# 4_LPC1850__Others.net
KiCad netlist of a schematic drawn in Altium Designer
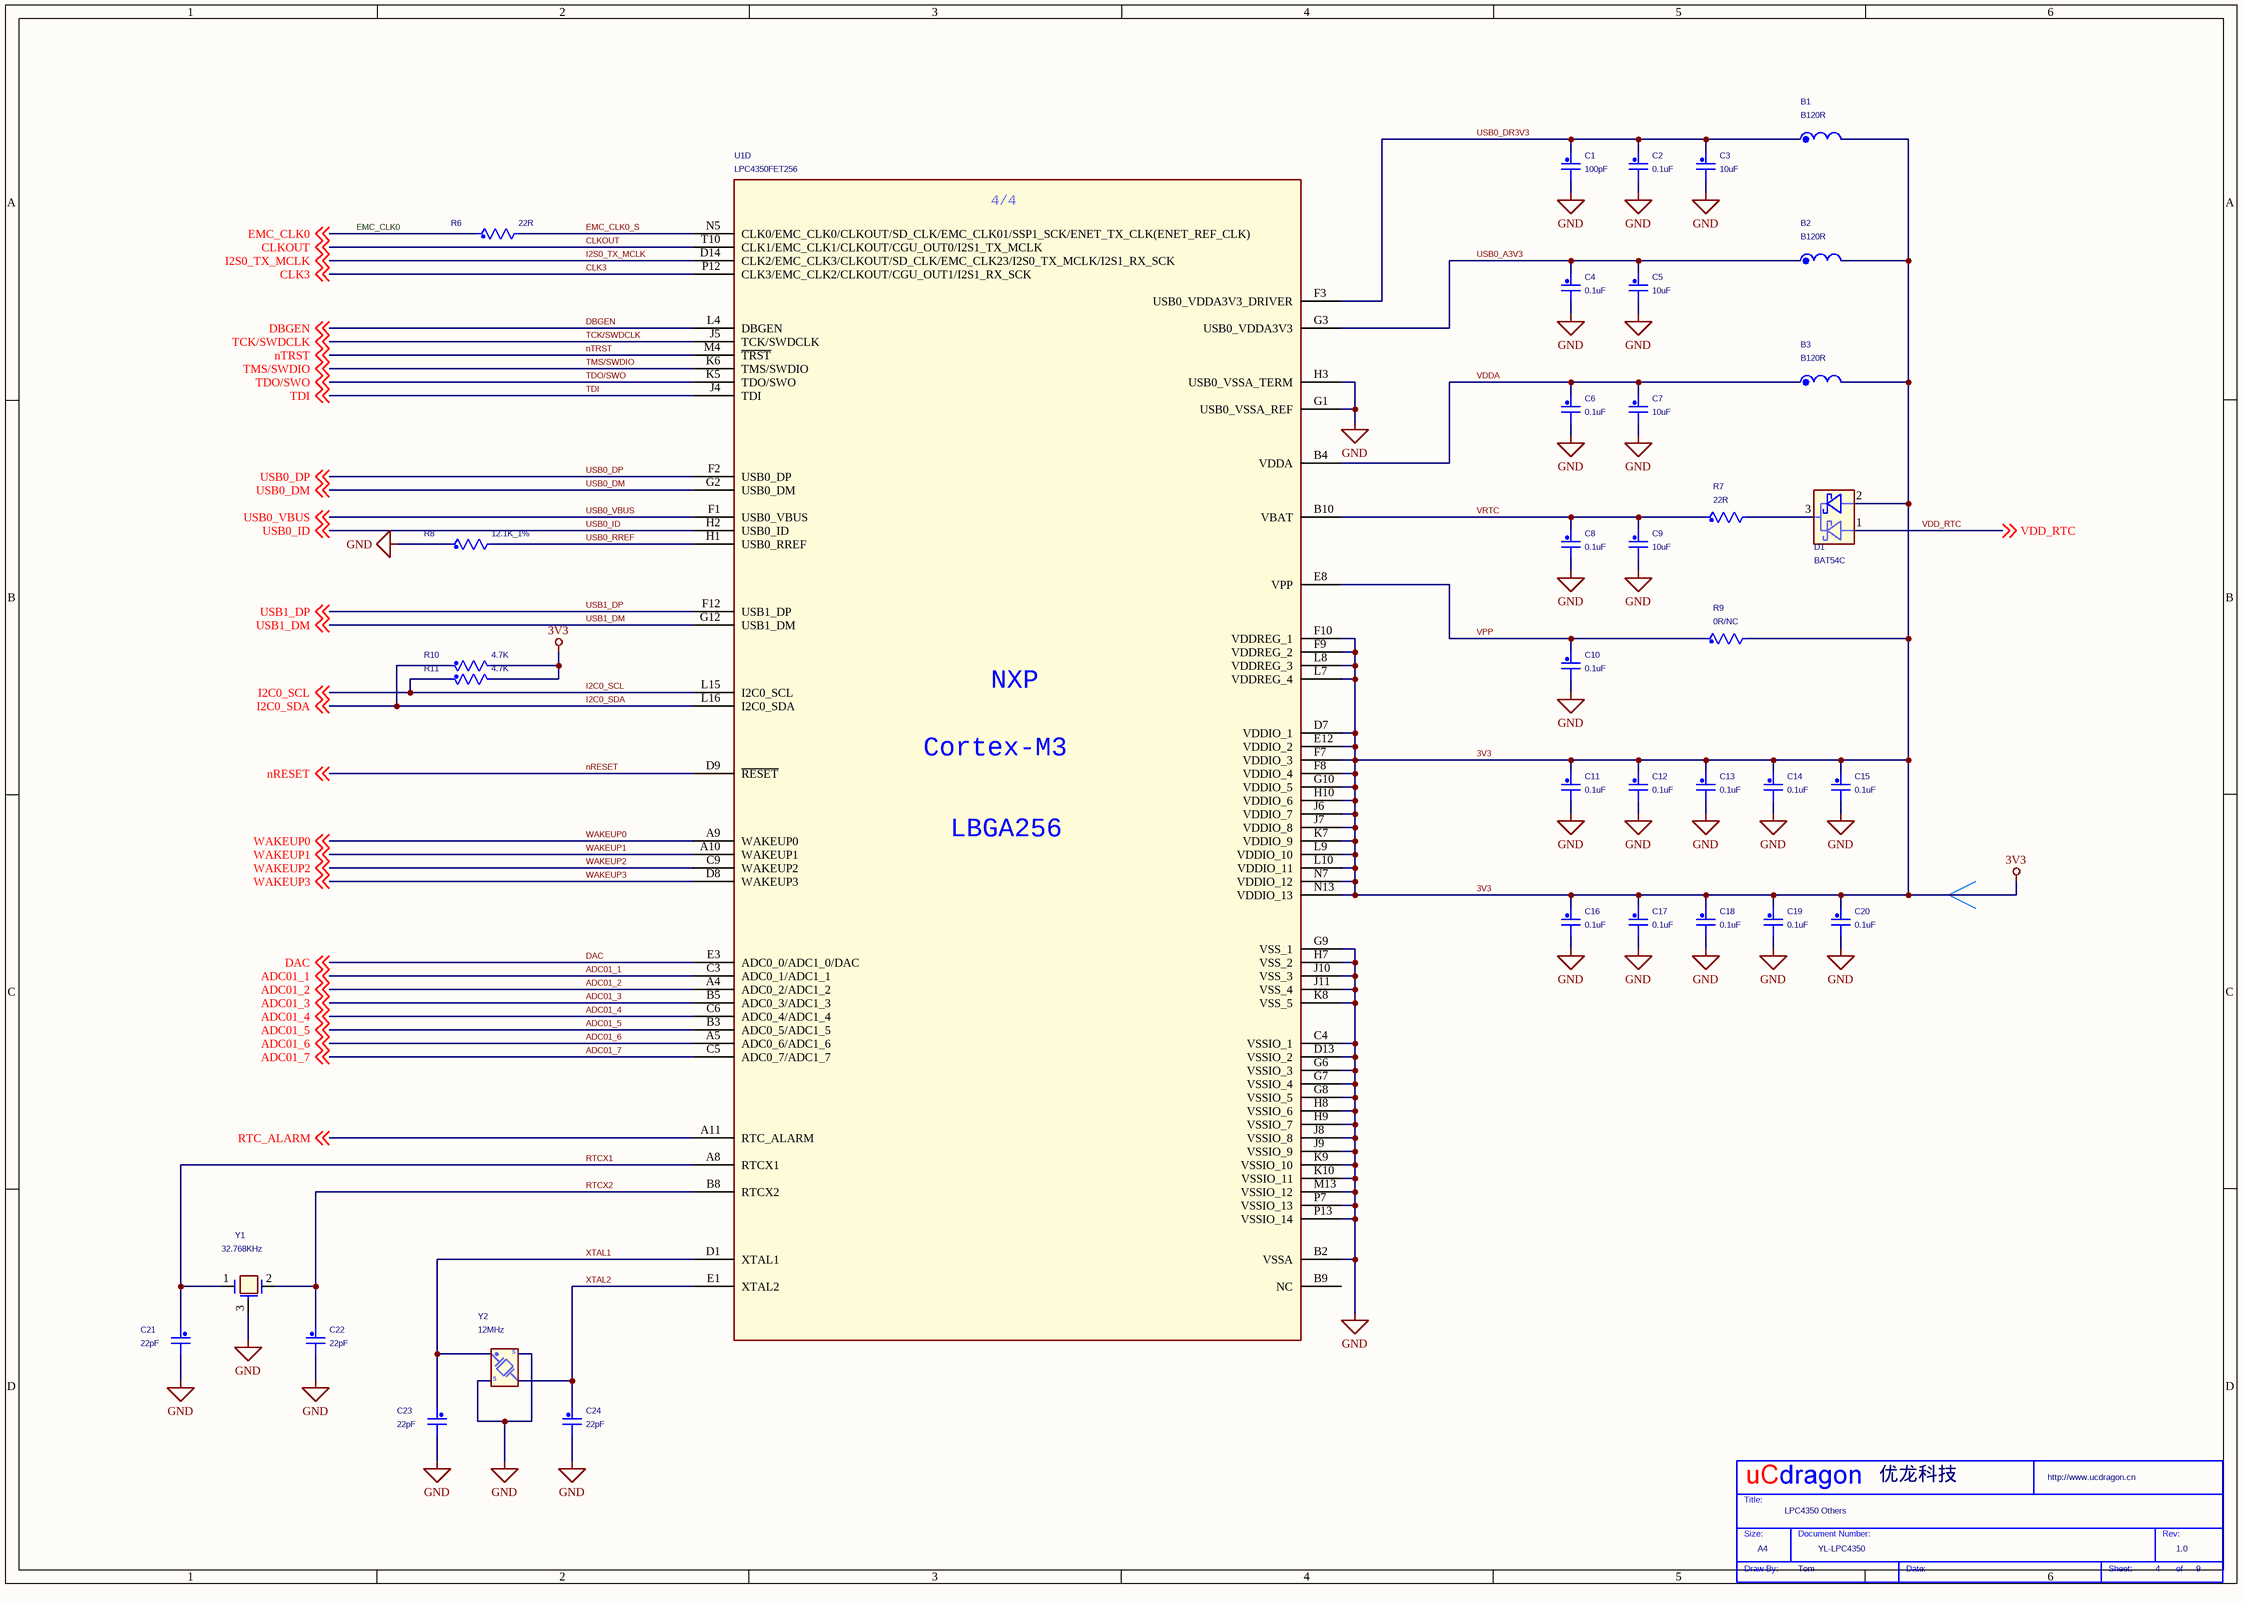
[diagram p0: 4) LPC1850_ Others.SchDoc]

(export (version "E")
  (design (tool "Eeschema 10.0.6"))
  (components
    (comp (ref "*")
      (value "My Title 0")
      (fields
        (field (name "COMPANY") "优龙科技")
        (field (name "DRAWING") "Tom")
        (field (name "WEBSITE") "http://www.ucdragon.cn")
        (field (name "DOC") "YL-LPC4350")
        (field (name "REVCODE") "1.0")
        (field (name "TITLE") "LPC4350 Others")
        (field (name "PAGE SIZE") "A4")
        (field (name "PAGE NUMBER") "4")
        (field (name "PAGE COUNT") "9")
      )
      (libsource (lib "*") (part "My Title 0"))
    )
    (comp (ref "B1") (value "B120R") (libsource (lib "*") (part "Inductor PWR-SMD")))
    (comp (ref "B2") (value "B120R") (libsource (lib "*") (part "Inductor PWR-SMD")))
    (comp (ref "B3") (value "B120R") (libsource (lib "*") (part "Inductor PWR-SMD")))
    (comp (ref "C1")
      (value "100pF")
      (footprint "CAP0805")
      (fields (field (name "VOLTAGE") "16V"))
      (libsource (lib "*") (part "C_Generic"))
    )
    (comp (ref "C2")
      (value "0.1uF")
      (footprint "CAP0805")
      (fields (field (name "VOLTAGE") "16V"))
      (libsource (lib "*") (part "C_Generic"))
    )
    (comp (ref "C3")
      (value "10uF")
      (footprint "CAP0805")
      (fields (field (name "VOLTAGE") "16V"))
      (libsource (lib "*") (part "C_Generic"))
    )
    (comp (ref "C4")
      (value "0.1uF")
      (footprint "CAP0805")
      (fields (field (name "VOLTAGE") "16V"))
      (libsource (lib "*") (part "C_Generic"))
    )
    (comp (ref "C5")
      (value "10uF")
      (footprint "CAP0805")
      (fields (field (name "VOLTAGE") "16V"))
      (libsource (lib "*") (part "C_Generic"))
    )
    (comp (ref "C6")
      (value "0.1uF")
      (footprint "CAP0805")
      (fields (field (name "VOLTAGE") "16V"))
      (libsource (lib "*") (part "C_Generic"))
    )
    (comp (ref "C7")
      (value "10uF")
      (footprint "CAP0805")
      (fields (field (name "VOLTAGE") "16V"))
      (libsource (lib "*") (part "C_Generic"))
    )
    (comp (ref "C8")
      (value "0.1uF")
      (footprint "CAP0805")
      (fields (field (name "VOLTAGE") "16V"))
      (libsource (lib "*") (part "C_Generic"))
    )
    (comp (ref "C9")
      (value "10uF")
      (footprint "CAP0805")
      (fields (field (name "VOLTAGE") "16V"))
      (libsource (lib "*") (part "C_Generic"))
    )
    (comp (ref "C10")
      (value "0.1uF")
      (footprint "CAP0805")
      (fields (field (name "VOLTAGE") "16V"))
      (libsource (lib "*") (part "C_Generic"))
    )
    (comp (ref "C11")
      (value "0.1uF")
      (footprint "CAP0805")
      (fields (field (name "VOLTAGE") "16V"))
      (libsource (lib "*") (part "C_Generic"))
    )
    (comp (ref "C12")
      (value "0.1uF")
      (footprint "CAP0805")
      (fields (field (name "VOLTAGE") "16V"))
      (libsource (lib "*") (part "C_Generic"))
    )
    (comp (ref "C13")
      (value "0.1uF")
      (footprint "CAP0805")
      (fields (field (name "VOLTAGE") "16V"))
      (libsource (lib "*") (part "C_Generic"))
    )
    (comp (ref "C14")
      (value "0.1uF")
      (footprint "CAP0805")
      (fields (field (name "VOLTAGE") "16V"))
      (libsource (lib "*") (part "C_Generic"))
    )
    (comp (ref "C15")
      (value "0.1uF")
      (footprint "CAP0805")
      (fields (field (name "VOLTAGE") "16V"))
      (libsource (lib "*") (part "C_Generic"))
    )
    (comp (ref "C16")
      (value "0.1uF")
      (footprint "CAP0805")
      (fields (field (name "VOLTAGE") "16V"))
      (libsource (lib "*") (part "C_Generic"))
    )
    (comp (ref "C17")
      (value "0.1uF")
      (footprint "CAP0805")
      (fields (field (name "VOLTAGE") "16V"))
      (libsource (lib "*") (part "C_Generic"))
    )
    (comp (ref "C18")
      (value "0.1uF")
      (footprint "CAP0805")
      (fields (field (name "VOLTAGE") "16V"))
      (libsource (lib "*") (part "C_Generic"))
    )
    (comp (ref "C19")
      (value "0.1uF")
      (footprint "CAP0805")
      (fields (field (name "VOLTAGE") "16V"))
      (libsource (lib "*") (part "C_Generic"))
    )
    (comp (ref "C20")
      (value "0.1uF")
      (footprint "CAP0805")
      (fields (field (name "VOLTAGE") "16V"))
      (libsource (lib "*") (part "C_Generic"))
    )
    (comp (ref "C21")
      (value "22pF")
      (footprint "CAP0805")
      (fields (field (name "VOLTAGE") "16V"))
      (libsource (lib "*") (part "C_Generic"))
    )
    (comp (ref "C22")
      (value "22pF")
      (footprint "CAP0805")
      (fields (field (name "VOLTAGE") "16V"))
      (libsource (lib "*") (part "C_Generic"))
    )
    (comp (ref "C23")
      (value "22pF")
      (footprint "CAP0805")
      (fields (field (name "VOLTAGE") "16V"))
      (libsource (lib "*") (part "C_Generic"))
    )
    (comp (ref "C24")
      (value "22pF")
      (footprint "CAP0805")
      (fields (field (name "VOLTAGE") "16V"))
      (libsource (lib "*") (part "C_Generic"))
    )
    (comp (ref "D1") (value "BAT54C") (libsource (lib "*") (part "BAT54C")))
    (comp (ref "R6") (value "22R") (libsource (lib "*") (part "R_Generic_Dup2")))
    (comp (ref "R7") (value "22R") (libsource (lib "*") (part "R_Generic_Dup2")))
    (comp (ref "R8") (value "12.1K_1%") (libsource (lib "*") (part "R_Generic_Dup2")))
    (comp (ref "R9") (value "0R/NC") (libsource (lib "*") (part "R_Generic_Dup2")))
    (comp (ref "R10") (value "4.7K") (libsource (lib "*") (part "R_Generic_Dup1")))
    (comp (ref "R11") (value "4.7K") (libsource (lib "*") (part "R_Generic_Dup1")))
    (comp (ref "U1")
      (value "LPC4350FET256")
      (footprint "LBGA256")
      (libsource (lib "*") (part "LPC4350FET256"))
    )
    (comp (ref "Y1") (value "32.768KHz") (libsource (lib "*") (part "XTAL1")))
    (comp (ref "Y2") (value "12MHz") (footprint "Y3225") (libsource (lib "*") (part "CRYSTAL 3225-2")))
  )
  (nets
    (net (code "1") (name "/EMC_CLK0_S") (class "Default")
      (node (ref "R6") (pin "2") (pinfunction "2_2") (pintype "passive"))
      (node (ref "U1") (pin "N5") (pinfunction "CLK0/EMC_CLK0/CLKOUT/SD_CLK/EMC_CLK01/SSP1_SCK/ENET_TX_CLK(ENET_REF_CLK)_N5") (pintype "passive"))
    )
    (net (code "2") (name "/RTCX1") (class "Default")
      (node (ref "C21") (pin "1") (pinfunction "1_1") (pintype "passive"))
      (node (ref "U1") (pin "A8") (pinfunction "RTCX1_A8") (pintype "passive"))
      (node (ref "Y1") (pin "1") (pinfunction "1_1") (pintype "passive"))
    )
    (net (code "3") (name "/RTCX2") (class "Default")
      (node (ref "C22") (pin "1") (pinfunction "1_1") (pintype "passive"))
      (node (ref "U1") (pin "B8") (pinfunction "RTCX2_B8") (pintype "passive"))
      (node (ref "Y1") (pin "2") (pinfunction "2_2") (pintype "passive"))
    )
    (net (code "4") (name "/USB0_A3V3") (class "Default")
      (node (ref "B2") (pin "1") (pinfunction "1_1") (pintype "passive"))
      (node (ref "C4") (pin "1") (pinfunction "1_1") (pintype "passive"))
      (node (ref "C5") (pin "1") (pinfunction "1_1") (pintype "passive"))
      (node (ref "U1") (pin "G3") (pinfunction "USB0_VDDA3V3_G3") (pintype "passive"))
    )
    (net (code "5") (name "/USB0_DR3V3") (class "Default")
      (node (ref "B1") (pin "1") (pinfunction "1_1") (pintype "passive"))
      (node (ref "C1") (pin "1") (pinfunction "1_1") (pintype "passive"))
      (node (ref "C2") (pin "1") (pinfunction "1_1") (pintype "passive"))
      (node (ref "C3") (pin "1") (pinfunction "1_1") (pintype "passive"))
      (node (ref "U1") (pin "F3") (pinfunction "USB0_VDDA3V3_DRIVER_F3") (pintype "passive"))
    )
    (net (code "6") (name "/USB0_RREF") (class "Default")
      (node (ref "R8") (pin "2") (pinfunction "2_2") (pintype "passive"))
      (node (ref "U1") (pin "H1") (pinfunction "USB0_RREF_H1") (pintype "passive"))
    )
    (net (code "7") (name "/VDDA") (class "Default")
      (node (ref "B3") (pin "1") (pinfunction "1_1") (pintype "passive"))
      (node (ref "C6") (pin "1") (pinfunction "1_1") (pintype "passive"))
      (node (ref "C7") (pin "1") (pinfunction "1_1") (pintype "passive"))
      (node (ref "U1") (pin "B4") (pinfunction "VDDA_B4") (pintype "passive"))
    )
    (net (code "8") (name "/VPP") (class "Default")
      (node (ref "C10") (pin "1") (pinfunction "1_1") (pintype "passive"))
      (node (ref "R9") (pin "1") (pinfunction "1_1") (pintype "passive"))
      (node (ref "U1") (pin "E8") (pinfunction "VPP_E8") (pintype "passive"))
    )
    (net (code "9") (name "/VRTC") (class "Default")
      (node (ref "C8") (pin "1") (pinfunction "1_1") (pintype "passive"))
      (node (ref "C9") (pin "1") (pinfunction "1_1") (pintype "passive"))
      (node (ref "R7") (pin "1") (pinfunction "1_1") (pintype "passive"))
      (node (ref "U1") (pin "B10") (pinfunction "VBAT_B10") (pintype "passive"))
    )
    (net (code "10") (name "/XTAL1") (class "Default")
      (node (ref "C23") (pin "1") (pinfunction "1_1") (pintype "passive"))
      (node (ref "U1") (pin "D1") (pinfunction "XTAL1_D1") (pintype "passive"))
      (node (ref "Y2") (pin "1") (pinfunction "1_1") (pintype "passive"))
    )
    (net (code "11") (name "/XTAL2") (class "Default")
      (node (ref "C24") (pin "1") (pinfunction "1_1") (pintype "passive"))
      (node (ref "U1") (pin "E1") (pinfunction "XTAL2_E1") (pintype "passive"))
      (node (ref "Y2") (pin "3") (pinfunction "3_3") (pintype "passive"))
    )
    (net (code "12") (name "3V3") (class "Default")
      (node (ref "B1") (pin "2") (pinfunction "2_2") (pintype "passive"))
      (node (ref "B2") (pin "2") (pinfunction "2_2") (pintype "passive"))
      (node (ref "B3") (pin "2") (pinfunction "2_2") (pintype "passive"))
      (node (ref "C11") (pin "1") (pinfunction "1_1") (pintype "passive"))
      (node (ref "C12") (pin "1") (pinfunction "1_1") (pintype "passive"))
      (node (ref "C13") (pin "1") (pinfunction "1_1") (pintype "passive"))
      (node (ref "C14") (pin "1") (pinfunction "1_1") (pintype "passive"))
      (node (ref "C15") (pin "1") (pinfunction "1_1") (pintype "passive"))
      (node (ref "C16") (pin "1") (pinfunction "1_1") (pintype "passive"))
      (node (ref "C17") (pin "1") (pinfunction "1_1") (pintype "passive"))
      (node (ref "C18") (pin "1") (pinfunction "1_1") (pintype "passive"))
      (node (ref "C19") (pin "1") (pinfunction "1_1") (pintype "passive"))
      (node (ref "C20") (pin "1") (pinfunction "1_1") (pintype "passive"))
      (node (ref "D1") (pin "2") (pinfunction "K_2") (pintype "passive"))
      (node (ref "R10") (pin "2") (pinfunction "2_2") (pintype "passive"))
      (node (ref "R11") (pin "2") (pinfunction "2_2") (pintype "passive"))
      (node (ref "R9") (pin "2") (pinfunction "2_2") (pintype "passive"))
      (node (ref "U1") (pin "D7") (pinfunction "VDDIO_1_D7") (pintype "passive"))
      (node (ref "U1") (pin "E12") (pinfunction "VDDIO_2_E12") (pintype "passive"))
      (node (ref "U1") (pin "F10") (pinfunction "VDDREG_1_F10") (pintype "passive"))
      (node (ref "U1") (pin "F7") (pinfunction "VDDIO_3_F7") (pintype "passive"))
      (node (ref "U1") (pin "F8") (pinfunction "VDDIO_4_F8") (pintype "passive"))
      (node (ref "U1") (pin "F9") (pinfunction "VDDREG_2_F9") (pintype "passive"))
      (node (ref "U1") (pin "G10") (pinfunction "VDDIO_5_G10") (pintype "passive"))
      (node (ref "U1") (pin "H10") (pinfunction "VDDIO_6_H10") (pintype "passive"))
      (node (ref "U1") (pin "J6") (pinfunction "VDDIO_7_J6") (pintype "passive"))
      (node (ref "U1") (pin "J7") (pinfunction "VDDIO_8_J7") (pintype "passive"))
      (node (ref "U1") (pin "K7") (pinfunction "VDDIO_9_K7") (pintype "passive"))
      (node (ref "U1") (pin "L10") (pinfunction "VDDIO_11_L10") (pintype "passive"))
      (node (ref "U1") (pin "L7") (pinfunction "VDDREG_4_L7") (pintype "passive"))
      (node (ref "U1") (pin "L8") (pinfunction "VDDREG_3_L8") (pintype "passive"))
      (node (ref "U1") (pin "L9") (pinfunction "VDDIO_10_L9") (pintype "passive"))
      (node (ref "U1") (pin "N13") (pinfunction "VDDIO_13_N13") (pintype "passive"))
      (node (ref "U1") (pin "N7") (pinfunction "VDDIO_12_N7") (pintype "passive"))
    )
    (net (code "13") (name "ADC01_1") (class "Default")
      (node (ref "U1") (pin "C3") (pinfunction "ADC0_1/ADC1_1_C3") (pintype "passive"))
    )
    (net (code "14") (name "ADC01_2") (class "Default")
      (node (ref "U1") (pin "A4") (pinfunction "ADC0_2/ADC1_2_A4") (pintype "passive"))
    )
    (net (code "15") (name "ADC01_3") (class "Default")
      (node (ref "U1") (pin "B5") (pinfunction "ADC0_3/ADC1_3_B5") (pintype "passive"))
    )
    (net (code "16") (name "ADC01_4") (class "Default")
      (node (ref "U1") (pin "C6") (pinfunction "ADC0_4/ADC1_4_C6") (pintype "passive"))
    )
    (net (code "17") (name "ADC01_5") (class "Default")
      (node (ref "U1") (pin "B3") (pinfunction "ADC0_5/ADC1_5_B3") (pintype "passive"))
    )
    (net (code "18") (name "ADC01_6") (class "Default")
      (node (ref "U1") (pin "A5") (pinfunction "ADC0_6/ADC1_6_A5") (pintype "passive"))
    )
    (net (code "19") (name "ADC01_7") (class "Default")
      (node (ref "U1") (pin "C5") (pinfunction "ADC0_7/ADC1_7_C5") (pintype "passive"))
    )
    (net (code "20") (name "CLK3") (class "Default")
      (node (ref "U1") (pin "P12") (pinfunction "CLK3/EMC_CLK2/CLKOUT/CGU_OUT1/I2S1_RX_SCK_P12") (pintype "passive"))
    )
    (net (code "21") (name "CLKOUT") (class "Default")
      (node (ref "U1") (pin "T10") (pinfunction "CLK1/EMC_CLK1/CLKOUT/CGU_OUT0/I2S1_TX_MCLK_T10") (pintype "passive"))
    )
    (net (code "22") (name "DAC") (class "Default")
      (node (ref "U1") (pin "E3") (pinfunction "ADC0_0/ADC1_0/DAC_E3") (pintype "passive"))
    )
    (net (code "23") (name "DBGEN") (class "Default")
      (node (ref "U1") (pin "L4") (pinfunction "DBGEN_L4") (pintype "passive"))
    )
    (net (code "24") (name "EMC_CLK0") (class "Default")
      (node (ref "R6") (pin "1") (pinfunction "1_1") (pintype "passive"))
    )
    (net (code "25") (name "GND") (class "Default")
      (node (ref "C1") (pin "2") (pinfunction "2_2") (pintype "passive"))
      (node (ref "C10") (pin "2") (pinfunction "2_2") (pintype "passive"))
      (node (ref "C11") (pin "2") (pinfunction "2_2") (pintype "passive"))
      (node (ref "C12") (pin "2") (pinfunction "2_2") (pintype "passive"))
      (node (ref "C13") (pin "2") (pinfunction "2_2") (pintype "passive"))
      (node (ref "C14") (pin "2") (pinfunction "2_2") (pintype "passive"))
      (node (ref "C15") (pin "2") (pinfunction "2_2") (pintype "passive"))
      (node (ref "C16") (pin "2") (pinfunction "2_2") (pintype "passive"))
      (node (ref "C17") (pin "2") (pinfunction "2_2") (pintype "passive"))
      (node (ref "C18") (pin "2") (pinfunction "2_2") (pintype "passive"))
      (node (ref "C19") (pin "2") (pinfunction "2_2") (pintype "passive"))
      (node (ref "C2") (pin "2") (pinfunction "2_2") (pintype "passive"))
      (node (ref "C20") (pin "2") (pinfunction "2_2") (pintype "passive"))
      (node (ref "C21") (pin "2") (pinfunction "2_2") (pintype "passive"))
      (node (ref "C22") (pin "2") (pinfunction "2_2") (pintype "passive"))
      (node (ref "C23") (pin "2") (pinfunction "2_2") (pintype "passive"))
      (node (ref "C24") (pin "2") (pinfunction "2_2") (pintype "passive"))
      (node (ref "C3") (pin "2") (pinfunction "2_2") (pintype "passive"))
      (node (ref "C4") (pin "2") (pinfunction "2_2") (pintype "passive"))
      (node (ref "C5") (pin "2") (pinfunction "2_2") (pintype "passive"))
      (node (ref "C6") (pin "2") (pinfunction "2_2") (pintype "passive"))
      (node (ref "C7") (pin "2") (pinfunction "2_2") (pintype "passive"))
      (node (ref "C8") (pin "2") (pinfunction "2_2") (pintype "passive"))
      (node (ref "C9") (pin "2") (pinfunction "2_2") (pintype "passive"))
      (node (ref "R8") (pin "1") (pinfunction "1_1") (pintype "passive"))
      (node (ref "U1") (pin "B2") (pinfunction "VSSA_B2") (pintype "passive"))
      (node (ref "U1") (pin "C4") (pinfunction "VSSIO_1_C4") (pintype "passive"))
      (node (ref "U1") (pin "D13") (pinfunction "VSSIO_2_D13") (pintype "passive"))
      (node (ref "U1") (pin "G1") (pinfunction "USB0_VSSA_REF_G1") (pintype "passive"))
      (node (ref "U1") (pin "G6") (pinfunction "VSSIO_3_G6") (pintype "passive"))
      (node (ref "U1") (pin "G7") (pinfunction "VSSIO_4_G7") (pintype "passive"))
      (node (ref "U1") (pin "G8") (pinfunction "VSSIO_5_G8") (pintype "passive"))
      (node (ref "U1") (pin "G9") (pinfunction "VSS_1_G9") (pintype "passive"))
      (node (ref "U1") (pin "H3") (pinfunction "USB0_VSSA_TERM_H3") (pintype "passive"))
      (node (ref "U1") (pin "H7") (pinfunction "VSS_2_H7") (pintype "passive"))
      (node (ref "U1") (pin "H8") (pinfunction "VSSIO_6_H8") (pintype "passive"))
      (node (ref "U1") (pin "H9") (pinfunction "VSSIO_7_H9") (pintype "passive"))
      (node (ref "U1") (pin "J10") (pinfunction "VSS_3_J10") (pintype "passive"))
      (node (ref "U1") (pin "J11") (pinfunction "VSS_4_J11") (pintype "passive"))
      (node (ref "U1") (pin "J8") (pinfunction "VSSIO_8_J8") (pintype "passive"))
      (node (ref "U1") (pin "J9") (pinfunction "VSSIO_9_J9") (pintype "passive"))
      (node (ref "U1") (pin "K10") (pinfunction "VSSIO_11_K10") (pintype "passive"))
      (node (ref "U1") (pin "K8") (pinfunction "VSS_5_K8") (pintype "passive"))
      (node (ref "U1") (pin "K9") (pinfunction "VSSIO_10_K9") (pintype "passive"))
      (node (ref "U1") (pin "M13") (pinfunction "VSSIO_12_M13") (pintype "passive"))
      (node (ref "U1") (pin "P13") (pinfunction "VSSIO_14_P13") (pintype "passive"))
      (node (ref "U1") (pin "P7") (pinfunction "VSSIO_13_P7") (pintype "passive"))
      (node (ref "Y1") (pin "3") (pinfunction "GND_3") (pintype "passive"))
      (node (ref "Y2") (pin "2") (pinfunction "2_2") (pintype "passive"))
      (node (ref "Y2") (pin "4") (pinfunction "4_4") (pintype "passive"))
    )
    (net (code "26") (name "I2C0_SCL") (class "Default")
      (node (ref "R11") (pin "1") (pinfunction "1_1") (pintype "passive"))
      (node (ref "U1") (pin "L15") (pinfunction "I2C0_SCL_L15") (pintype "passive"))
    )
    (net (code "27") (name "I2C0_SDA") (class "Default")
      (node (ref "R10") (pin "1") (pinfunction "1_1") (pintype "passive"))
      (node (ref "U1") (pin "L16") (pinfunction "I2C0_SDA_L16") (pintype "passive"))
    )
    (net (code "28") (name "I2S0_TX_MCLK") (class "Default")
      (node (ref "U1") (pin "D14") (pinfunction "CLK2/EMC_CLK3/CLKOUT/SD_CLK/EMC_CLK23/I2S0_TX_MCLK/I2S1_RX_SCK_D14") (pintype "passive"))
    )
    (net (code "29") (name "Net-(D1-COM)") (class "Default")
      (node (ref "D1") (pin "3") (pinfunction "COM_3") (pintype "passive"))
      (node (ref "R7") (pin "2") (pinfunction "2_2") (pintype "passive"))
    )
    (net (code "30") (name "RTC_ALARM") (class "Default")
      (node (ref "U1") (pin "A11") (pinfunction "RTC_ALARM_A11") (pintype "passive"))
    )
    (net (code "31") (name "TCK{slash}SWDCLK") (class "Default")
      (node (ref "U1") (pin "J5") (pinfunction "TCK/SWDCLK_J5") (pintype "passive"))
    )
    (net (code "32") (name "TDI") (class "Default")
      (node (ref "U1") (pin "J4") (pinfunction "TDI_J4") (pintype "passive"))
    )
    (net (code "33") (name "TDO{slash}SWO") (class "Default")
      (node (ref "U1") (pin "K5") (pinfunction "TDO/SWO_K5") (pintype "passive"))
    )
    (net (code "34") (name "TMS{slash}SWDIO") (class "Default")
      (node (ref "U1") (pin "K6") (pinfunction "TMS/SWDIO_K6") (pintype "passive"))
    )
    (net (code "35") (name "USB0_DM") (class "Default")
      (node (ref "U1") (pin "G2") (pinfunction "USB0_DM_G2") (pintype "passive"))
    )
    (net (code "36") (name "USB0_DP") (class "Default")
      (node (ref "U1") (pin "F2") (pinfunction "USB0_DP_F2") (pintype "passive"))
    )
    (net (code "37") (name "USB0_ID") (class "Default")
      (node (ref "U1") (pin "H2") (pinfunction "USB0_ID_H2") (pintype "passive"))
    )
    (net (code "38") (name "USB0_VBUS") (class "Default")
      (node (ref "U1") (pin "F1") (pinfunction "USB0_VBUS_F1") (pintype "passive"))
    )
    (net (code "39") (name "USB1_DM") (class "Default")
      (node (ref "U1") (pin "G12") (pinfunction "USB1_DM_G12") (pintype "passive"))
    )
    (net (code "40") (name "USB1_DP") (class "Default")
      (node (ref "U1") (pin "F12") (pinfunction "USB1_DP_F12") (pintype "passive"))
    )
    (net (code "41") (name "VDD_RTC") (class "Default")
      (node (ref "D1") (pin "1") (pinfunction "A_1") (pintype "passive"))
    )
    (net (code "42") (name "WAKEUP0") (class "Default")
      (node (ref "U1") (pin "A9") (pinfunction "WAKEUP0_A9") (pintype "passive"))
    )
    (net (code "43") (name "WAKEUP1") (class "Default")
      (node (ref "U1") (pin "A10") (pinfunction "WAKEUP1_A10") (pintype "passive"))
    )
    (net (code "44") (name "WAKEUP2") (class "Default")
      (node (ref "U1") (pin "C9") (pinfunction "WAKEUP2_C9") (pintype "passive"))
    )
    (net (code "45") (name "WAKEUP3") (class "Default")
      (node (ref "U1") (pin "D8") (pinfunction "WAKEUP3_D8") (pintype "passive"))
    )
    (net (code "46") (name "nRESET") (class "Default")
      (node (ref "U1") (pin "D9") (pinfunction "~{RESET}_D9") (pintype "passive"))
    )
    (net (code "47") (name "nTRST") (class "Default")
      (node (ref "U1") (pin "M4") (pinfunction "~{TRST}_M4") (pintype "passive"))
    )
    (net (code "48") (name "unconnected-(U1D-NC-PadB9)") (class "Default")
      (node (ref "U1") (pin "B9") (pinfunction "NC_B9") (pintype "passive"))
    )
  )
)
